# Safety_Loops.net
KiCad netlist of a schematic drawn in Altium Designer
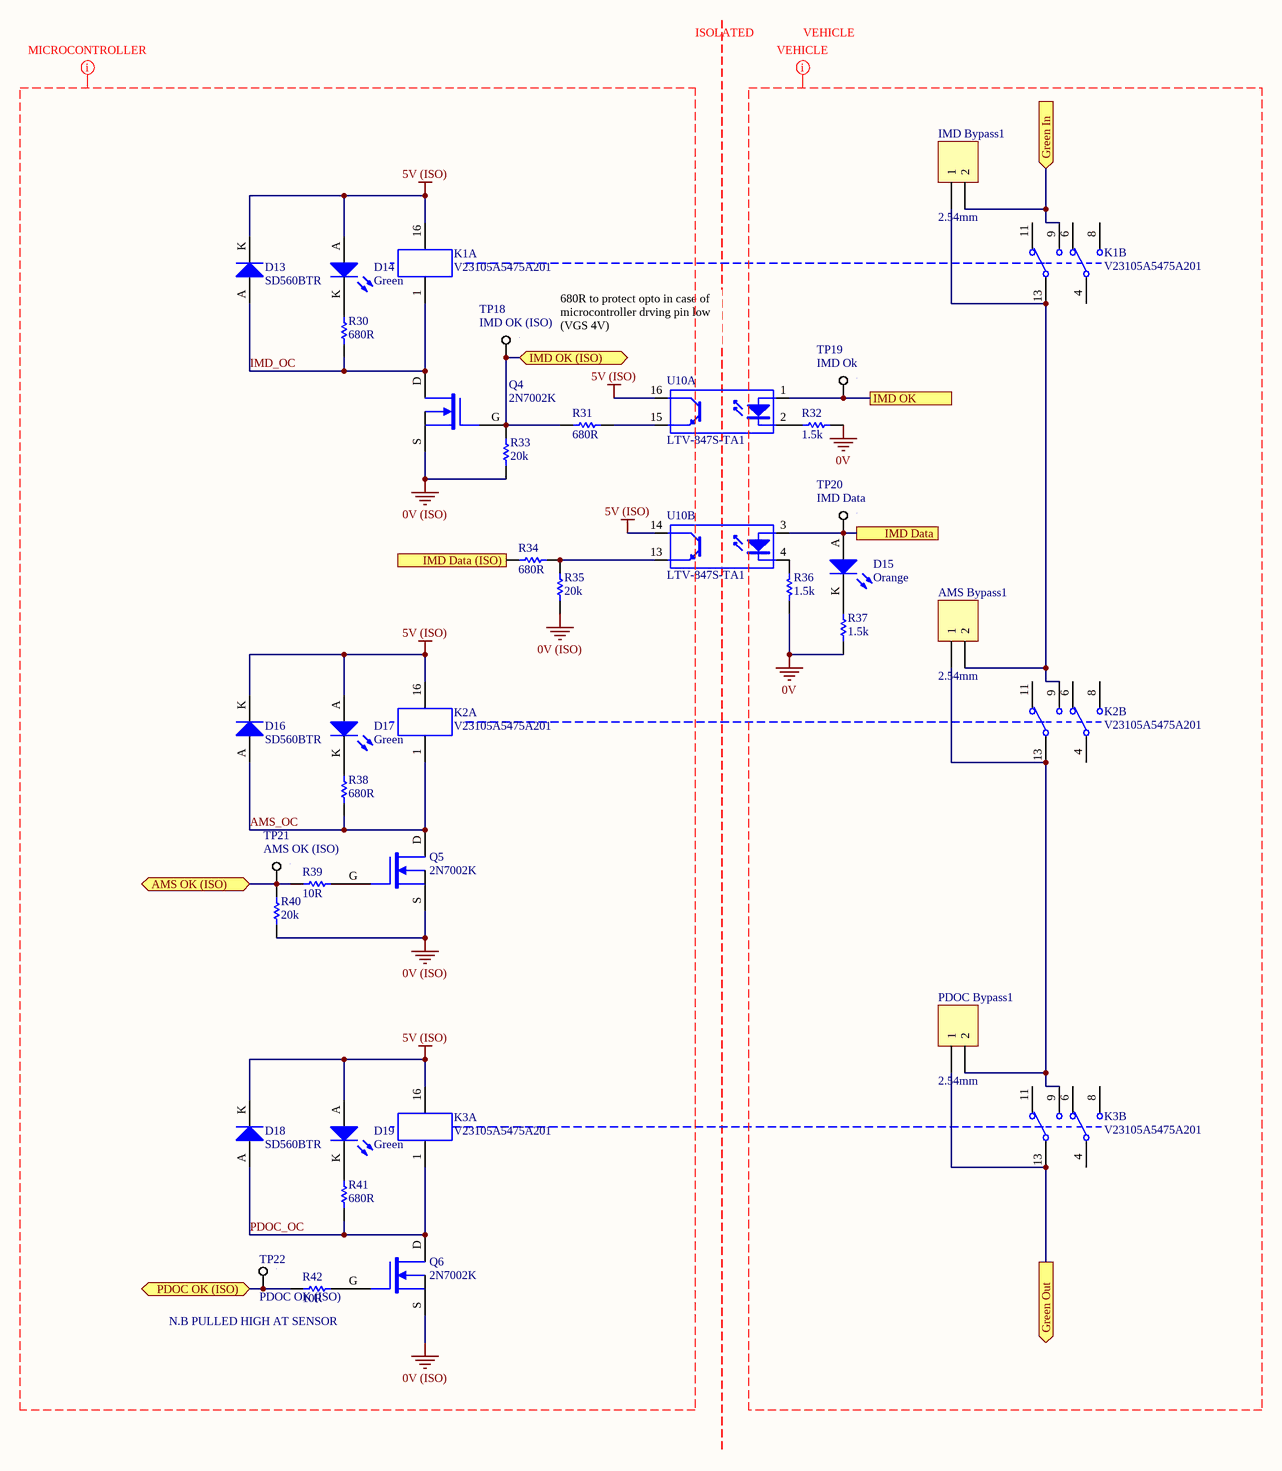
[diagram p0: Safety Loops.SchDoc]

(export (version "E")
  (design (tool "Eeschema 10.0.6"))
  (components
    (comp (ref "AMS Bypass1")
      (value "2.54mm")
      (footprint "TH 2.54mm Header 1x2")
      (fields (field (name "PART NUMBER") "TH 2.54mm Header 1x2") (field (name "CONTACT") "NA"))
      (libsource (lib "ts_20-standard-connectors") (part "Header 1x2"))
    )
    (comp (ref "D13")
      (value "SD560BTR")
      (footprint "SMB Diode")
      (description "1.2V_F 600V 5A SMB")
      (fields
        (field (name "MANUFACTURER") "SMC Diode Solutions")
        (field (name "DIGIKEY PART NUMBER") "1655-1530-2-ND")
      )
      (libsource (lib "ts_20-standard-library") (part "Diode"))
    )
    (comp (ref "D14")
      (value "Green")
      (footprint "0805 LED")
      (description "Green LED Indication - Discrete 1.75V 0805 (2012 Metric)")
      (fields (field (name "PART NUMBER") "SML-210FTT86") (field (name "MANUFACTURER") "ROHM Semiconductor"))
      (libsource (lib "ts_20-standard-library") (part "LED"))
    )
    (comp (ref "D15")
      (value "Orange")
      (footprint "0805 LED")
      (description "Orange LED Indication - Discrete 1.75V 0805 (2012 Metric)")
      (fields (field (name "PART NUMBER") "SML-211DTT86") (field (name "MANUFACTURER") "ROHM Semiconductor"))
      (libsource (lib "ts_20-standard-library") (part "LED"))
    )
    (comp (ref "D16")
      (value "SD560BTR")
      (footprint "SMB Diode")
      (description "1.2V_F 600V 5A SMB")
      (fields
        (field (name "MANUFACTURER") "SMC Diode Solutions")
        (field (name "DIGIKEY PART NUMBER") "1655-1530-2-ND")
      )
      (libsource (lib "ts_20-standard-library") (part "Diode"))
    )
    (comp (ref "D17")
      (value "Green")
      (footprint "0805 LED")
      (description "Green LED Indication - Discrete 1.75V 0805 (2012 Metric)")
      (fields (field (name "PART NUMBER") "SML-210FTT86") (field (name "MANUFACTURER") "ROHM Semiconductor"))
      (libsource (lib "ts_20-standard-library") (part "LED"))
    )
    (comp (ref "D18")
      (value "SD560BTR")
      (footprint "SMB Diode")
      (description "1.2V_F 600V 5A SMB")
      (fields
        (field (name "MANUFACTURER") "SMC Diode Solutions")
        (field (name "DIGIKEY PART NUMBER") "1655-1530-2-ND")
      )
      (libsource (lib "ts_20-standard-library") (part "Diode"))
    )
    (comp (ref "D19")
      (value "Green")
      (footprint "0805 LED")
      (description "Green LED Indication - Discrete 1.75V 0805 (2012 Metric)")
      (fields (field (name "PART NUMBER") "SML-210FTT86") (field (name "MANUFACTURER") "ROHM Semiconductor"))
      (libsource (lib "ts_20-standard-library") (part "LED"))
    )
    (comp (ref "IMD Bypass1")
      (value "2.54mm")
      (footprint "TH 2.54mm Header 1x2")
      (fields (field (name "PART NUMBER") "TH 2.54mm Header 1x2") (field (name "CONTACT") "NA"))
      (libsource (lib "ts_20-standard-connectors") (part "Header 1x2"))
    )
    (comp (ref "K1")
      (value "V23105A5475A201")
      (footprint "TI 2-DIL")
      (description "5V DPDT Relay 3A 220VDC")
      (fields (field (name "MANUFACTURER") "Axicom") (field (name "DIGIKEY PART NUMBER") "PB383-ND"))
      (libsource (lib "ts_20-standard-library") (part "V23105A5475A201"))
    )
    (comp (ref "K2")
      (value "V23105A5475A201")
      (footprint "TI 2-DIL")
      (description "5V DPDT Relay 3A 220VDC")
      (fields (field (name "MANUFACTURER") "Axicom") (field (name "DIGIKEY PART NUMBER") "PB383-ND"))
      (libsource (lib "") (part "V23105A5475A201_1"))
    )
    (comp (ref "K3")
      (value "V23105A5475A201")
      (footprint "TI 2-DIL")
      (description "5V DPDT Relay 3A 220VDC")
      (fields (field (name "MANUFACTURER") "Axicom") (field (name "DIGIKEY PART NUMBER") "PB383-ND"))
      (libsource (lib "ts_20-standard-library") (part "V23105A5475A201"))
    )
    (comp (ref "PDOC Bypass1")
      (value "2.54mm")
      (footprint "TH 2.54mm Header 1x2")
      (fields (field (name "PART NUMBER") "TH 2.54mm Header 1x2") (field (name "CONTACT") "NA"))
      (libsource (lib "ts_20-standard-connectors") (part "Header 1x2"))
    )
    (comp (ref "Q4")
      (value "2N7002K")
      (footprint "ON SOT-23 MOSFET")
      (description "60V 380mA, NFET MOSTFET (Small Signal)")
      (fields
        (field (name "MANUFACTURER") "ON Semiconductor")
        (field (name "DIGIKEY PART NUMBER") "2N7002KCT-ND")
        (field (name "PUBLISHER") "Altium Limited")
      )
      (libsource (lib "ts_20-standard-library") (part "MOSFET-N"))
    )
    (comp (ref "Q5")
      (value "2N7002K")
      (footprint "ON SOT-23 MOSFET")
      (description "60V 380mA, NFET MOSTFET (Small Signal)")
      (fields
        (field (name "MANUFACTURER") "ON Semiconductor")
        (field (name "DIGIKEY PART NUMBER") "2N7002KCT-ND")
        (field (name "PUBLISHER") "Altium Limited")
      )
      (libsource (lib "ts_20-standard-library") (part "MOSFET-N"))
    )
    (comp (ref "Q6")
      (value "2N7002K")
      (footprint "ON SOT-23 MOSFET")
      (description "60V 380mA, NFET MOSTFET (Small Signal)")
      (fields
        (field (name "MANUFACTURER") "ON Semiconductor")
        (field (name "DIGIKEY PART NUMBER") "2N7002KCT-ND")
        (field (name "PUBLISHER") "Altium Limited")
      )
      (libsource (lib "ts_20-standard-library") (part "MOSFET-N"))
    )
    (comp (ref "R30")
      (value "680R")
      (footprint "0805")
      (fields
        (field (name "PART NUMBER") "RC0805FR07680RL")
        (field (name "MANUFACTURER") "YAGEO")
        (field (name "TOLERANCE") "0.01")
      )
      (libsource (lib "ts_20-standard-library") (part "Resistor"))
    )
    (comp (ref "R31")
      (value "680R")
      (footprint "0805")
      (fields
        (field (name "PART NUMBER") "RC0805FR07680RL")
        (field (name "MANUFACTURER") "YAGEO")
        (field (name "TOLERANCE") "0.01")
      )
      (libsource (lib "ts_20-standard-library") (part "Resistor"))
    )
    (comp (ref "R32")
      (value "1.5k")
      (footprint "0805")
      (fields
        (field (name "PART NUMBER") "RC0805FR071K5L")
        (field (name "MANUFACTURER") "YAGEO")
        (field (name "TOLERANCE") "0.01")
      )
      (libsource (lib "ts_20-standard-library") (part "Resistor"))
    )
    (comp (ref "R33")
      (value "20k")
      (footprint "0805")
      (fields
        (field (name "PART NUMBER") "RC0805FR0720KL")
        (field (name "MANUFACTURER") "YAGEO")
        (field (name "TOLERANCE") "0.01")
      )
      (libsource (lib "ts_20-standard-library") (part "Resistor"))
    )
    (comp (ref "R34")
      (value "680R")
      (footprint "0805")
      (fields
        (field (name "PART NUMBER") "RC0805FR07680RL")
        (field (name "MANUFACTURER") "YAGEO")
        (field (name "TOLERANCE") "0.01")
      )
      (libsource (lib "ts_20-standard-library") (part "Resistor"))
    )
    (comp (ref "R35")
      (value "20k")
      (footprint "0805")
      (fields
        (field (name "PART NUMBER") "RC0805FR0720KL")
        (field (name "MANUFACTURER") "YAGEO")
        (field (name "TOLERANCE") "0.01")
      )
      (libsource (lib "ts_20-standard-library") (part "Resistor"))
    )
    (comp (ref "R36")
      (value "1.5k")
      (footprint "0805")
      (fields
        (field (name "PART NUMBER") "RC0805FR071K5L")
        (field (name "MANUFACTURER") "YAGEO")
        (field (name "TOLERANCE") "0.01")
      )
      (libsource (lib "ts_20-standard-library") (part "Resistor"))
    )
    (comp (ref "R37")
      (value "1.5k")
      (footprint "0805")
      (fields
        (field (name "PART NUMBER") "RC0805FR071K5L")
        (field (name "MANUFACTURER") "YAGEO")
        (field (name "TOLERANCE") "0.01")
      )
      (libsource (lib "ts_20-standard-library") (part "Resistor"))
    )
    (comp (ref "R38")
      (value "680R")
      (footprint "0805")
      (fields
        (field (name "PART NUMBER") "RC0805FR07680RL")
        (field (name "MANUFACTURER") "YAGEO")
        (field (name "TOLERANCE") "0.01")
      )
      (libsource (lib "ts_20-standard-library") (part "Resistor"))
    )
    (comp (ref "R39")
      (value "10R")
      (footprint "0805")
      (fields
        (field (name "PART NUMBER") "RC0805FR0710RL")
        (field (name "MANUFACTURER") "YAGEO")
        (field (name "TOLERANCE") "0.01")
      )
      (libsource (lib "ts_20-standard-library") (part "Resistor"))
    )
    (comp (ref "R40")
      (value "20k")
      (footprint "0805")
      (fields
        (field (name "PART NUMBER") "RC0805FR0720KL")
        (field (name "MANUFACTURER") "YAGEO")
        (field (name "TOLERANCE") "0.01")
      )
      (libsource (lib "ts_20-standard-library") (part "Resistor"))
    )
    (comp (ref "R41")
      (value "680R")
      (footprint "0805")
      (fields
        (field (name "PART NUMBER") "RC0805FR07680RL")
        (field (name "MANUFACTURER") "YAGEO")
        (field (name "TOLERANCE") "0.01")
      )
      (libsource (lib "ts_20-standard-library") (part "Resistor"))
    )
    (comp (ref "R42")
      (value "10R")
      (footprint "0805")
      (fields
        (field (name "PART NUMBER") "RC0805FR0710RL")
        (field (name "MANUFACTURER") "YAGEO")
        (field (name "TOLERANCE") "0.01")
      )
      (libsource (lib "ts_20-standard-library") (part "Resistor"))
    )
    (comp (ref "TP18")
      (value "IMD OK (ISO)")
      (footprint "SMD Test Point 1mm")
      (fields (field (name "PART NUMBER") "SMD Test Point Small") (field (name "CONTACT") "NA"))
      (libsource (lib "ts_20-standard-connectors") (part "Test Point Small"))
    )
    (comp (ref "TP19")
      (value "IMD Ok")
      (footprint "SMD Test Point 1mm")
      (fields (field (name "PART NUMBER") "SMD Test Point Small") (field (name "CONTACT") "NA"))
      (libsource (lib "ts_20-standard-connectors") (part "Test Point Small"))
    )
    (comp (ref "TP20")
      (value "IMD Data")
      (footprint "SMD Test Point 1mm")
      (fields (field (name "PART NUMBER") "SMD Test Point Small") (field (name "CONTACT") "NA"))
      (libsource (lib "ts_20-standard-connectors") (part "Test Point Small"))
    )
    (comp (ref "TP21")
      (value "AMS OK (ISO)")
      (footprint "SMD Test Point 1mm")
      (fields (field (name "PART NUMBER") "SMD Test Point Small") (field (name "CONTACT") "NA"))
      (libsource (lib "ts_20-standard-connectors") (part "Test Point Small"))
    )
    (comp (ref "TP22")
      (value "PDOC OK (ISO)")
      (footprint "SMD Test Point 1mm")
      (fields (field (name "PART NUMBER") "SMD Test Point Small") (field (name "CONTACT") "NA"))
      (libsource (lib "ts_20-standard-connectors") (part "Test Point Small"))
    )
    (comp (ref "U10")
      (value "LTV-847S-TA1")
      (footprint "ON 16-SMD")
      (description "Optoisolator Transistor Output 5000Vrms 4 Channel 16-SMD")
      (fields
        (field (name "MANUFACTURER") "Lite-On Inc")
        (field (name "DIGIKEY PART NUMBER") "160-1371-5-ND")
      )
      (libsource (lib "ts_20-standard-library") (part "LTV-847S-TA1"))
    )
  )
  (nets
    (net (code "1") (name "/AMS OK (ISO)") (class "Default")
      (node (ref "R39") (pin "1") (pinfunction "1_1") (pintype "passive"))
      (node (ref "R40") (pin "2") (pinfunction "2_2") (pintype "passive"))
      (node (ref "TP21") (pin "1") (pinfunction "1_1") (pintype "passive"))
    )
    (net (code "2") (name "/AMS_OC") (class "Default")
      (node (ref "D16") (pin "A") (pinfunction "A_A") (pintype "passive"))
      (node (ref "K2") (pin "1") (pinfunction "1_1") (pintype "passive"))
      (node (ref "Q5") (pin "D") (pinfunction "D_D") (pintype "passive"))
      (node (ref "R38") (pin "1") (pinfunction "1_1") (pintype "passive"))
    )
    (net (code "3") (name "/Green In") (class "Default")
      (node (ref "IMD Bypass1") (pin "2") (pinfunction "2_2") (pintype "passive"))
      (node (ref "K1") (pin "9") (pinfunction "9_9") (pintype "passive"))
    )
    (net (code "4") (name "/Green Out") (class "Default")
      (node (ref "K3") (pin "13") (pinfunction "13_13") (pintype "passive"))
      (node (ref "PDOC Bypass1") (pin "1") (pinfunction "1_1") (pintype "passive"))
    )
    (net (code "5") (name "/IMD Data") (class "Default")
      (node (ref "D15") (pin "A") (pinfunction "A_A") (pintype "passive"))
      (node (ref "TP20") (pin "1") (pinfunction "1_1") (pintype "passive"))
      (node (ref "U10") (pin "3") (pinfunction "A_3") (pintype "passive"))
    )
    (net (code "6") (name "/IMD Data (ISO)") (class "Default")
      (node (ref "R34") (pin "1") (pinfunction "1_1") (pintype "passive"))
    )
    (net (code "7") (name "/IMD OK") (class "Default")
      (node (ref "TP19") (pin "1") (pinfunction "1_1") (pintype "passive"))
      (node (ref "U10") (pin "1") (pinfunction "A_1") (pintype "passive"))
    )
    (net (code "8") (name "/IMD OK (ISO)") (class "Default")
      (node (ref "Q4") (pin "G") (pinfunction "G_G") (pintype "passive"))
      (node (ref "R31") (pin "1") (pinfunction "1_1") (pintype "passive"))
      (node (ref "R33") (pin "2") (pinfunction "2_2") (pintype "passive"))
      (node (ref "TP18") (pin "1") (pinfunction "1_1") (pintype "passive"))
    )
    (net (code "9") (name "/IMD_OC") (class "Default")
      (node (ref "D13") (pin "A") (pinfunction "A_A") (pintype "passive"))
      (node (ref "K1") (pin "1") (pinfunction "1_1") (pintype "passive"))
      (node (ref "Q4") (pin "D") (pinfunction "D_D") (pintype "passive"))
      (node (ref "R30") (pin "1") (pinfunction "1_1") (pintype "passive"))
    )
    (net (code "10") (name "/PDOC OK (ISO)") (class "Default")
      (node (ref "R42") (pin "1") (pinfunction "1_1") (pintype "passive"))
      (node (ref "TP22") (pin "1") (pinfunction "1_1") (pintype "passive"))
    )
    (net (code "11") (name "/PDOC_OC") (class "Default")
      (node (ref "D18") (pin "A") (pinfunction "A_A") (pintype "passive"))
      (node (ref "K3") (pin "1") (pinfunction "1_1") (pintype "passive"))
      (node (ref "Q6") (pin "D") (pinfunction "D_D") (pintype "passive"))
      (node (ref "R41") (pin "1") (pinfunction "1_1") (pintype "passive"))
    )
    (net (code "12") (name "0V") (class "Default")
      (node (ref "R32") (pin "1") (pinfunction "1_1") (pintype "passive"))
      (node (ref "R36") (pin "2") (pinfunction "2_2") (pintype "passive"))
      (node (ref "R37") (pin "2") (pinfunction "2_2") (pintype "passive"))
    )
    (net (code "13") (name "0V (ISO)") (class "Default")
      (node (ref "Q4") (pin "S") (pinfunction "S_S") (pintype "passive"))
      (node (ref "Q5") (pin "S") (pinfunction "S_S") (pintype "passive"))
      (node (ref "Q6") (pin "S") (pinfunction "S_S") (pintype "passive"))
      (node (ref "R33") (pin "1") (pinfunction "1_1") (pintype "passive"))
      (node (ref "R35") (pin "1") (pinfunction "1_1") (pintype "passive"))
      (node (ref "R40") (pin "1") (pinfunction "1_1") (pintype "passive"))
    )
    (net (code "14") (name "5V (ISO)") (class "Default")
      (node (ref "D13") (pin "K") (pinfunction "K_K") (pintype "passive"))
      (node (ref "D14") (pin "A") (pinfunction "A_A") (pintype "passive"))
      (node (ref "D16") (pin "K") (pinfunction "K_K") (pintype "passive"))
      (node (ref "D17") (pin "A") (pinfunction "A_A") (pintype "passive"))
      (node (ref "D18") (pin "K") (pinfunction "K_K") (pintype "passive"))
      (node (ref "D19") (pin "A") (pinfunction "A_A") (pintype "passive"))
      (node (ref "K1") (pin "16") (pinfunction "16_16") (pintype "passive"))
      (node (ref "K2") (pin "16") (pinfunction "16_16") (pintype "passive"))
      (node (ref "K3") (pin "16") (pinfunction "16_16") (pintype "passive"))
      (node (ref "U10") (pin "14") (pinfunction "C_14") (pintype "passive"))
      (node (ref "U10") (pin "16") (pinfunction "C_16") (pintype "passive"))
    )
    (net (code "15") (name "Net-(AMS Bypass1-Pad1)") (class "Default")
      (node (ref "AMS Bypass1") (pin "1") (pinfunction "1_1") (pintype "passive"))
      (node (ref "K2") (pin "13") (pinfunction "13_13") (pintype "passive"))
      (node (ref "K3") (pin "9") (pinfunction "9_9") (pintype "passive"))
      (node (ref "PDOC Bypass1") (pin "2") (pinfunction "2_2") (pintype "passive"))
    )
    (net (code "16") (name "Net-(AMS Bypass1-Pad2)") (class "Default")
      (node (ref "AMS Bypass1") (pin "2") (pinfunction "2_2") (pintype "passive"))
      (node (ref "IMD Bypass1") (pin "1") (pinfunction "1_1") (pintype "passive"))
      (node (ref "K1") (pin "13") (pinfunction "13_13") (pintype "passive"))
      (node (ref "K2") (pin "9") (pinfunction "9_9") (pintype "passive"))
    )
    (net (code "17") (name "Net-(D14-PadK)") (class "Default")
      (node (ref "D14") (pin "K") (pinfunction "K_K") (pintype "passive"))
      (node (ref "R30") (pin "2") (pinfunction "2_2") (pintype "passive"))
    )
    (net (code "18") (name "Net-(D15-PadK)") (class "Default")
      (node (ref "D15") (pin "K") (pinfunction "K_K") (pintype "passive"))
      (node (ref "R37") (pin "1") (pinfunction "1_1") (pintype "passive"))
    )
    (net (code "19") (name "Net-(D17-PadK)") (class "Default")
      (node (ref "D17") (pin "K") (pinfunction "K_K") (pintype "passive"))
      (node (ref "R38") (pin "2") (pinfunction "2_2") (pintype "passive"))
    )
    (net (code "20") (name "Net-(D19-PadK)") (class "Default")
      (node (ref "D19") (pin "K") (pinfunction "K_K") (pintype "passive"))
      (node (ref "R41") (pin "2") (pinfunction "2_2") (pintype "passive"))
    )
    (net (code "21") (name "Net-(Q5-PadG)") (class "Default")
      (node (ref "Q5") (pin "G") (pinfunction "G_G") (pintype "passive"))
      (node (ref "R39") (pin "2") (pinfunction "2_2") (pintype "passive"))
    )
    (net (code "22") (name "Net-(Q6-PadG)") (class "Default")
      (node (ref "Q6") (pin "G") (pinfunction "G_G") (pintype "passive"))
      (node (ref "R42") (pin "2") (pinfunction "2_2") (pintype "passive"))
    )
    (net (code "23") (name "Net-(U10A-E)") (class "Default")
      (node (ref "R31") (pin "2") (pinfunction "2_2") (pintype "passive"))
      (node (ref "U10") (pin "15") (pinfunction "E_15") (pintype "passive"))
    )
    (net (code "24") (name "Net-(U10A-K)") (class "Default")
      (node (ref "R32") (pin "2") (pinfunction "2_2") (pintype "passive"))
      (node (ref "U10") (pin "2") (pinfunction "K_2") (pintype "passive"))
    )
    (net (code "25") (name "Net-(U10B-E)") (class "Default")
      (node (ref "R34") (pin "2") (pinfunction "2_2") (pintype "passive"))
      (node (ref "R35") (pin "2") (pinfunction "2_2") (pintype "passive"))
      (node (ref "U10") (pin "13") (pinfunction "E_13") (pintype "passive"))
    )
    (net (code "26") (name "Net-(U10B-K)") (class "Default")
      (node (ref "R36") (pin "1") (pinfunction "1_1") (pintype "passive"))
      (node (ref "U10") (pin "4") (pinfunction "K_4") (pintype "passive"))
    )
    (net (code "27") (name "unconnected-(K1-Pad4)") (class "Default")
      (node (ref "K1") (pin "4") (pinfunction "4_4") (pintype "passive"))
    )
    (net (code "28") (name "unconnected-(K1-Pad6)") (class "Default")
      (node (ref "K1") (pin "6") (pinfunction "6_6") (pintype "passive"))
    )
    (net (code "29") (name "unconnected-(K1-Pad8)") (class "Default")
      (node (ref "K1") (pin "8") (pinfunction "8_8") (pintype "passive"))
    )
    (net (code "30") (name "unconnected-(K1-Pad11)") (class "Default")
      (node (ref "K1") (pin "11") (pinfunction "11_11") (pintype "passive"))
    )
    (net (code "31") (name "unconnected-(K2-Pad4)") (class "Default")
      (node (ref "K2") (pin "4") (pinfunction "4_4") (pintype "passive"))
    )
    (net (code "32") (name "unconnected-(K2-Pad6)") (class "Default")
      (node (ref "K2") (pin "6") (pinfunction "6_6") (pintype "passive"))
    )
    (net (code "33") (name "unconnected-(K2-Pad8)") (class "Default")
      (node (ref "K2") (pin "8") (pinfunction "8_8") (pintype "passive"))
    )
    (net (code "34") (name "unconnected-(K2-Pad11)") (class "Default")
      (node (ref "K2") (pin "11") (pinfunction "11_11") (pintype "passive"))
    )
    (net (code "35") (name "unconnected-(K3-Pad4)") (class "Default")
      (node (ref "K3") (pin "4") (pinfunction "4_4") (pintype "passive"))
    )
    (net (code "36") (name "unconnected-(K3-Pad6)") (class "Default")
      (node (ref "K3") (pin "6") (pinfunction "6_6") (pintype "passive"))
    )
    (net (code "37") (name "unconnected-(K3-Pad8)") (class "Default")
      (node (ref "K3") (pin "8") (pinfunction "8_8") (pintype "passive"))
    )
    (net (code "38") (name "unconnected-(K3-Pad11)") (class "Default")
      (node (ref "K3") (pin "11") (pinfunction "11_11") (pintype "passive"))
    )
  )
)
